# ESP32.net
KiCad netlist of a schematic drawn in Altium Designer
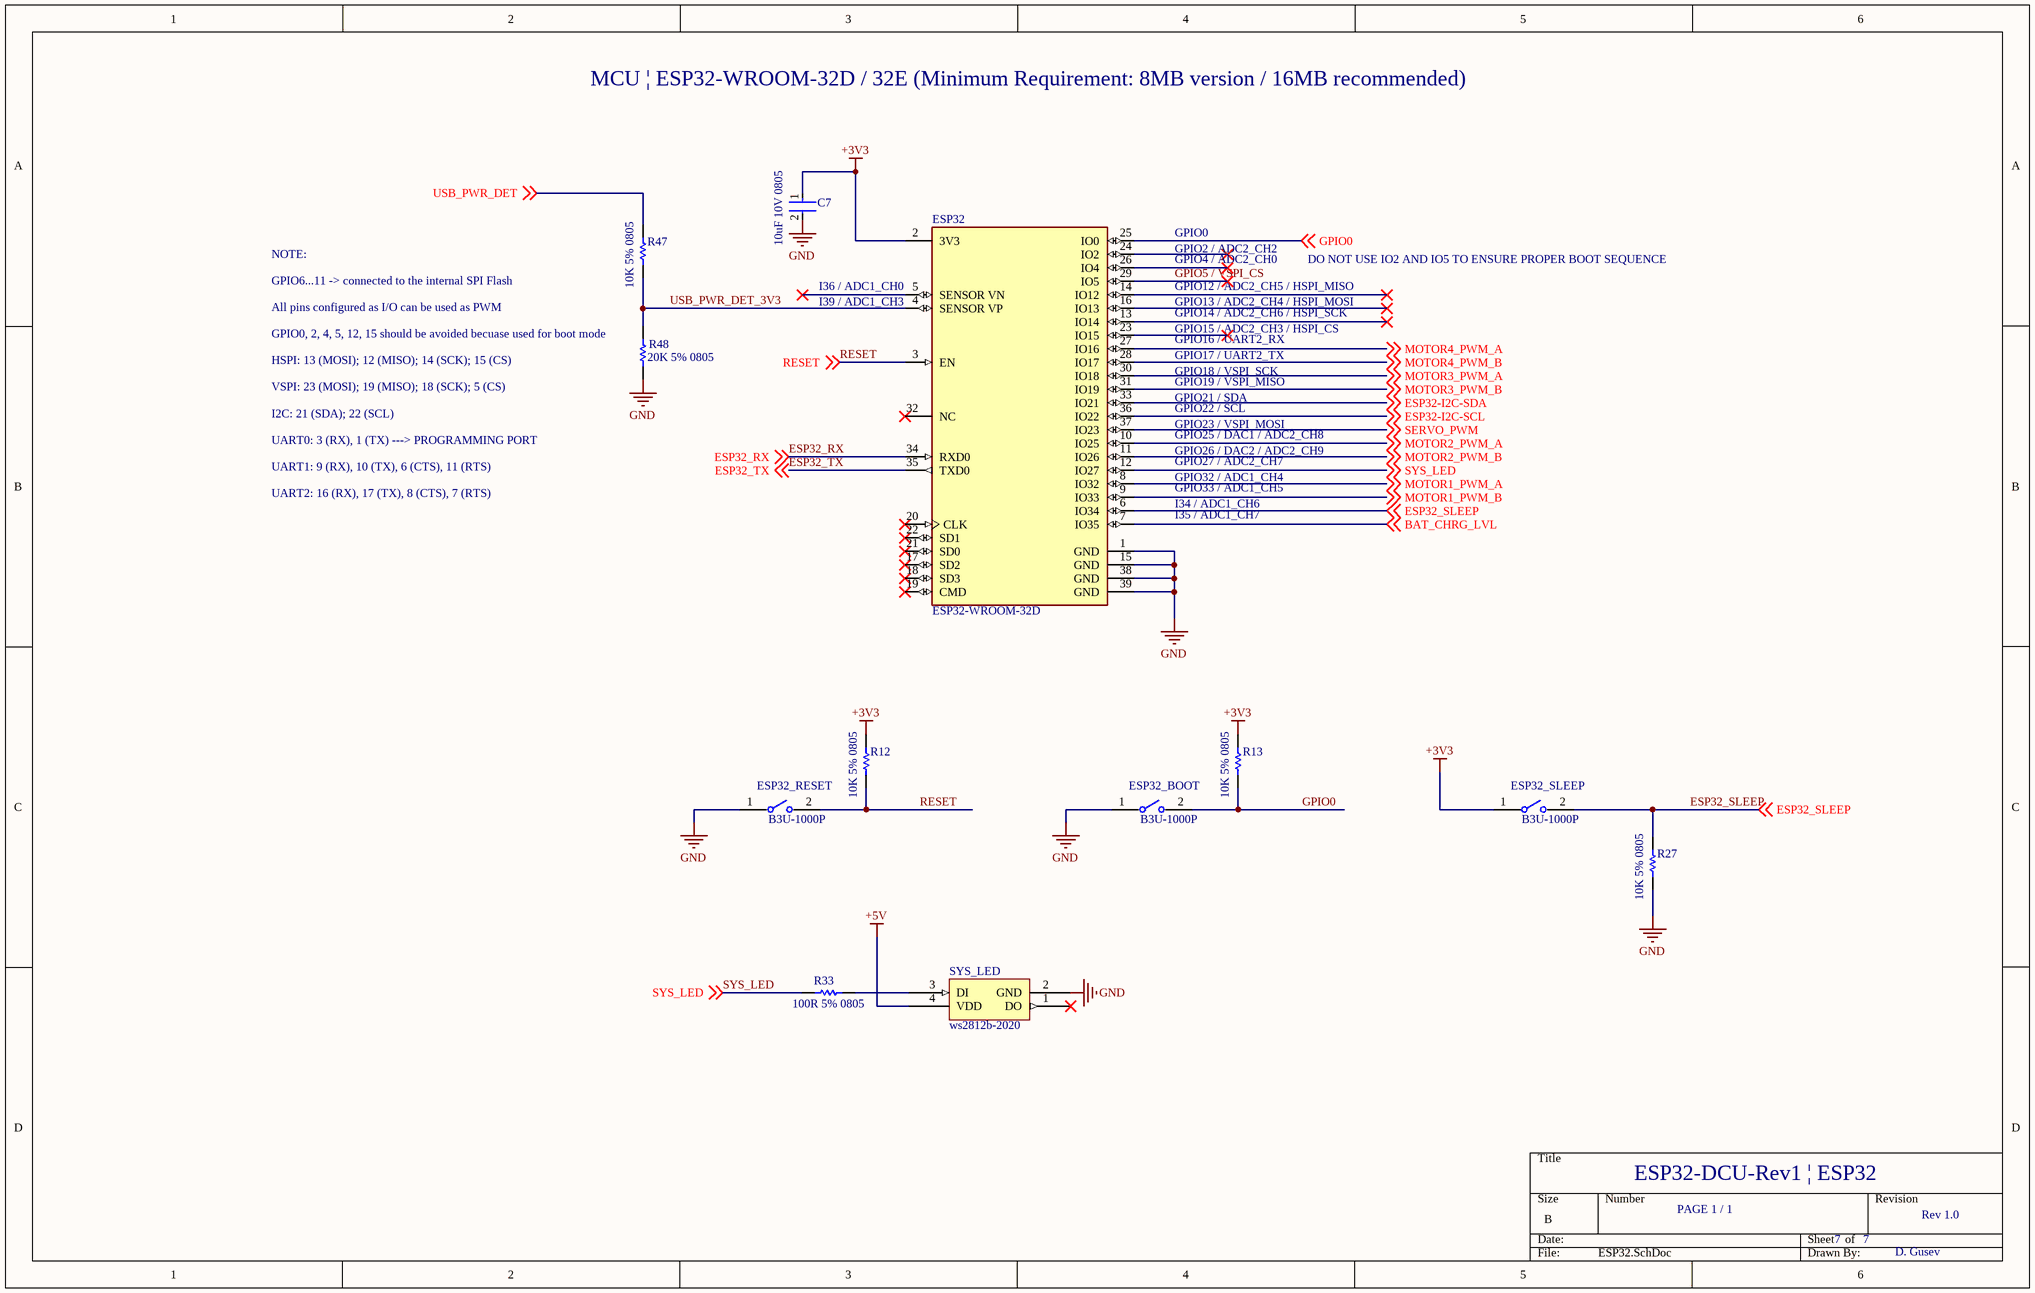
[diagram p0: ESP32.SchDoc]

(export (version "E")
  (design (tool "Eeschema 10.0.6"))
  (components
    (comp (ref "C7")
      (value "10uF 10V 0805")
      (footprint "FP-C0805C-DG-MFG")
      (description "CAP CER 10UF 10V X5R 0805")
      (fields (field (name "TOLERANCE") "10%") (field (name "MANUFACTURER PART NUMBER") "C0805C106K8PACTU"))
      (libsource (lib "Altium Content Vault") (part "11868f565c42a9108669ba33697ecf6"))
    )
    (comp (ref "ESP32")
      (value "ESP32-WROOM-32D")
      (footprint "ESP32-WROOM-U")
      (description "WIFI MODULE 32MBITS SPI FLASH")
      (fields
        (field (name "OCTOPART") "https://octopart.com/esp32-wroom-32d-espressif+systems-91040050")
        (field (name "MANUFACTURER") "Espressif Systems")
      )
      (libsource (lib "ddrlegobrick") (part "ESP32-WROOM-U"))
    )
    (comp (ref "ESP32_BOOT")
      (value "B3U-1000P")
      (footprint "FP-B3U-1000P-MFG")
      (description "SWITCH TACTILE SPST-NO 0.05A 12V")
      (libsource (lib "Altium Content Vault") (part "ae622034201233ca1abcedc05908f33"))
    )
    (comp (ref "ESP32_RESET")
      (value "B3U-1000P")
      (footprint "FP-B3U-1000P-MFG")
      (description "SWITCH TACTILE SPST-NO 0.05A 12V")
      (libsource (lib "Altium Content Vault") (part "ae622034201233ca1abcedc05908f33"))
    )
    (comp (ref "ESP32_SLEEP")
      (value "B3U-1000P")
      (footprint "FP-B3U-1000P-MFG")
      (description "SWITCH TACTILE SPST-NO 0.05A 12V")
      (libsource (lib "Altium Content Vault") (part "ae622034201233ca1abcedc05908f33"))
    )
    (comp (ref "R12")
      (value "10K 5% 0805")
      (footprint "RESC2013X60X40ML20T25")
      (fields (field (name "PART NUMBER") "ERA6AEB123V") (field (name "MANUFACTURER") "Panasonic"))
      (libsource (lib "Altium Content Vault") (part "RES"))
    )
    (comp (ref "R13")
      (value "10K 5% 0805")
      (footprint "RESC2013X60X40ML20T25")
      (fields (field (name "PART NUMBER") "ERA6AEB123V") (field (name "MANUFACTURER") "Panasonic"))
      (libsource (lib "Altium Content Vault") (part "RES"))
    )
    (comp (ref "R27")
      (value "10K 5% 0805")
      (footprint "RESC2013X60X40ML20T25")
      (fields (field (name "PART NUMBER") "ERA6AEB123V") (field (name "MANUFACTURER") "Panasonic"))
      (libsource (lib "Altium Content Vault") (part "RES"))
    )
    (comp (ref "R33")
      (value "100R 5% 0805")
      (footprint "RESC2013X60X35ML10T20")
      (description "Chip Resistor, 100 Ohm, +/-1%, 0.125 W, -55 to 155 degC, 0805 (2012 Metric), RoHS, Tape and Reel")
      (fields (field (name "TOLERANCE") "1%") (field (name "MANUFACTURER") "Yageo"))
      (libsource (lib "Altium Content Vault") (part "RES-2"))
    )
    (comp (ref "R47")
      (value "10K 5% 0805")
      (footprint "RESC2013X60X40ML20T25")
      (fields (field (name "PART NUMBER") "ERA6AEB123V") (field (name "MANUFACTURER") "Panasonic"))
      (libsource (lib "Altium Content Vault") (part "RES"))
    )
    (comp (ref "R48")
      (value "20K 5% 0805")
      (footprint "RESC0805(2012)_N")
      (description "20K 0.125W 1% 0805 (2012 Metric)  SMD")
      (fields (field (name "POWER") "0.125 W") (field (name "TOLERANCE") "1 %"))
      (libsource (lib "Altium Content Vault") (part "RES"))
    )
    (comp (ref "SYS_LED")
      (value "ws2812b-2020")
      (footprint "ws2812b")
      (libsource (lib "ddrlegobrick") (part "ws2812b-2020"))
    )
  )
  (nets
    (net (code "1") (name "+3V3") (class "Default")
      (node (ref "C7") (pin "1") (pinfunction "1_1") (pintype "passive"))
      (node (ref "ESP32") (pin "2") (pinfunction "3V3_2") (pintype "power_in"))
      (node (ref "ESP32_SLEEP") (pin "1") (pinfunction "1_1") (pintype "passive"))
      (node (ref "R12") (pin "2") (pinfunction "2_2") (pintype "passive"))
      (node (ref "R13") (pin "2") (pinfunction "2_2") (pintype "passive"))
    )
    (net (code "2") (name "+5V") (class "Default")
      (node (ref "SYS_LED") (pin "4") (pinfunction "VDD_4") (pintype "power_in"))
    )
    (net (code "3") (name "/GPIO5 {slash} VSPI_CS") (class "Default")
      (node (ref "ESP32") (pin "29") (pinfunction "IO5_29") (pintype "bidirectional+no_connect"))
    )
    (net (code "4") (name "/USB_PWR_DET_3V3") (class "Default")
      (node (ref "ESP32") (pin "4") (pinfunction "SENSOR_VP_4") (pintype "bidirectional"))
      (node (ref "R47") (pin "1") (pinfunction "1_1") (pintype "passive"))
      (node (ref "R48") (pin "2") (pinfunction "2_2") (pintype "passive"))
    )
    (net (code "5") (name "BAT_CHRG_LVL") (class "Default")
      (node (ref "ESP32") (pin "7") (pinfunction "IO35_7") (pintype "bidirectional"))
    )
    (net (code "6") (name "ESP32-I2C-SCL") (class "Default")
      (node (ref "ESP32") (pin "36") (pinfunction "IO22_36") (pintype "bidirectional"))
    )
    (net (code "7") (name "ESP32-I2C-SDA") (class "Default")
      (node (ref "ESP32") (pin "33") (pinfunction "IO21_33") (pintype "bidirectional"))
    )
    (net (code "8") (name "ESP32_RX") (class "Default")
      (node (ref "ESP32") (pin "34") (pinfunction "RXD0_34") (pintype "input"))
    )
    (net (code "9") (name "ESP32_SLEEP") (class "Default")
      (node (ref "ESP32") (pin "6") (pinfunction "IO34_6") (pintype "bidirectional"))
      (node (ref "ESP32_SLEEP") (pin "2") (pinfunction "2_2") (pintype "passive"))
      (node (ref "R27") (pin "2") (pinfunction "2_2") (pintype "passive"))
    )
    (net (code "10") (name "ESP32_TX") (class "Default")
      (node (ref "ESP32") (pin "35") (pinfunction "TXD0_35") (pintype "output"))
    )
    (net (code "11") (name "GND") (class "Default")
      (node (ref "C7") (pin "2") (pinfunction "2_2") (pintype "passive"))
      (node (ref "ESP32") (pin "1") (pinfunction "GND_1") (pintype "power_in"))
      (node (ref "ESP32") (pin "15") (pinfunction "GND_15") (pintype "power_in"))
      (node (ref "ESP32") (pin "38") (pinfunction "GND_38") (pintype "power_in"))
      (node (ref "ESP32") (pin "39") (pinfunction "GND_39") (pintype "power_in"))
      (node (ref "ESP32_BOOT") (pin "1") (pinfunction "1_1") (pintype "passive"))
      (node (ref "ESP32_RESET") (pin "1") (pinfunction "1_1") (pintype "passive"))
      (node (ref "R27") (pin "1") (pinfunction "1_1") (pintype "passive"))
      (node (ref "R48") (pin "1") (pinfunction "1_1") (pintype "passive"))
      (node (ref "SYS_LED") (pin "2") (pinfunction "GND_2") (pintype "passive"))
    )
    (net (code "12") (name "GPIO0") (class "Default")
      (node (ref "ESP32") (pin "25") (pinfunction "IO0_25") (pintype "bidirectional"))
      (node (ref "ESP32_BOOT") (pin "2") (pinfunction "2_2") (pintype "passive"))
      (node (ref "R13") (pin "1") (pinfunction "1_1") (pintype "passive"))
    )
    (net (code "13") (name "MOTOR1_PWM_A") (class "Default")
      (node (ref "ESP32") (pin "8") (pinfunction "IO32_8") (pintype "bidirectional"))
    )
    (net (code "14") (name "MOTOR1_PWM_B") (class "Default")
      (node (ref "ESP32") (pin "9") (pinfunction "IO33_9") (pintype "bidirectional"))
    )
    (net (code "15") (name "MOTOR2_PWM_A") (class "Default")
      (node (ref "ESP32") (pin "10") (pinfunction "IO25_10") (pintype "bidirectional"))
    )
    (net (code "16") (name "MOTOR2_PWM_B") (class "Default")
      (node (ref "ESP32") (pin "11") (pinfunction "IO26_11") (pintype "bidirectional"))
    )
    (net (code "17") (name "MOTOR3_PWM_A") (class "Default")
      (node (ref "ESP32") (pin "30") (pinfunction "IO18_30") (pintype "bidirectional"))
    )
    (net (code "18") (name "MOTOR3_PWM_B") (class "Default")
      (node (ref "ESP32") (pin "31") (pinfunction "IO19_31") (pintype "bidirectional"))
    )
    (net (code "19") (name "MOTOR4_PWM_A") (class "Default")
      (node (ref "ESP32") (pin "27") (pinfunction "IO16_27") (pintype "bidirectional"))
    )
    (net (code "20") (name "MOTOR4_PWM_B") (class "Default")
      (node (ref "ESP32") (pin "28") (pinfunction "IO17_28") (pintype "bidirectional"))
    )
    (net (code "21") (name "Net-(SYS_LED-DI)") (class "Default")
      (node (ref "R33") (pin "2") (pinfunction "2_2") (pintype "passive"))
      (node (ref "SYS_LED") (pin "3") (pinfunction "DI_3") (pintype "input"))
    )
    (net (code "22") (name "RESET") (class "Default")
      (node (ref "ESP32") (pin "3") (pinfunction "EN_3") (pintype "input"))
      (node (ref "ESP32_RESET") (pin "2") (pinfunction "2_2") (pintype "passive"))
      (node (ref "R12") (pin "1") (pinfunction "1_1") (pintype "passive"))
    )
    (net (code "23") (name "SERVO_PWM") (class "Default")
      (node (ref "ESP32") (pin "37") (pinfunction "IO23_37") (pintype "bidirectional"))
    )
    (net (code "24") (name "SYS_LED") (class "Default")
      (node (ref "ESP32") (pin "12") (pinfunction "IO27_12") (pintype "bidirectional"))
      (node (ref "R33") (pin "1") (pinfunction "1_1") (pintype "passive"))
    )
    (net (code "25") (name "USB_PWR_DET") (class "Default")
      (node (ref "R47") (pin "2") (pinfunction "2_2") (pintype "passive"))
    )
    (net (code "26") (name "unconnected-(ESP32-CLK-Pad20)") (class "Default")
      (node (ref "ESP32") (pin "20") (pinfunction "CLK_20") (pintype "input+no_connect"))
    )
    (net (code "27") (name "unconnected-(ESP32-CMD-Pad19)") (class "Default")
      (node (ref "ESP32") (pin "19") (pinfunction "CMD_19") (pintype "bidirectional+no_connect"))
    )
    (net (code "28") (name "unconnected-(ESP32-IO2-Pad24)") (class "Default")
      (node (ref "ESP32") (pin "24") (pinfunction "IO2_24") (pintype "bidirectional+no_connect"))
    )
    (net (code "29") (name "unconnected-(ESP32-IO4-Pad26)") (class "Default")
      (node (ref "ESP32") (pin "26") (pinfunction "IO4_26") (pintype "bidirectional+no_connect"))
    )
    (net (code "30") (name "unconnected-(ESP32-IO12-Pad14)") (class "Default")
      (node (ref "ESP32") (pin "14") (pinfunction "IO12_14") (pintype "bidirectional+no_connect"))
    )
    (net (code "31") (name "unconnected-(ESP32-IO13-Pad16)") (class "Default")
      (node (ref "ESP32") (pin "16") (pinfunction "IO13_16") (pintype "bidirectional+no_connect"))
    )
    (net (code "32") (name "unconnected-(ESP32-IO14-Pad13)") (class "Default")
      (node (ref "ESP32") (pin "13") (pinfunction "IO14_13") (pintype "bidirectional+no_connect"))
    )
    (net (code "33") (name "unconnected-(ESP32-IO15-Pad23)") (class "Default")
      (node (ref "ESP32") (pin "23") (pinfunction "IO15_23") (pintype "bidirectional+no_connect"))
    )
    (net (code "34") (name "unconnected-(ESP32-NC-Pad32)") (class "Default")
      (node (ref "ESP32") (pin "32") (pinfunction "NC_32") (pintype "passive+no_connect"))
    )
    (net (code "35") (name "unconnected-(ESP32-SD0-Pad21)") (class "Default")
      (node (ref "ESP32") (pin "21") (pinfunction "SD0_21") (pintype "bidirectional+no_connect"))
    )
    (net (code "36") (name "unconnected-(ESP32-SD1-Pad22)") (class "Default")
      (node (ref "ESP32") (pin "22") (pinfunction "SD1_22") (pintype "bidirectional+no_connect"))
    )
    (net (code "37") (name "unconnected-(ESP32-SD2-Pad17)") (class "Default")
      (node (ref "ESP32") (pin "17") (pinfunction "SD2_17") (pintype "bidirectional+no_connect"))
    )
    (net (code "38") (name "unconnected-(ESP32-SD3-Pad18)") (class "Default")
      (node (ref "ESP32") (pin "18") (pinfunction "SD3_18") (pintype "bidirectional+no_connect"))
    )
    (net (code "39") (name "unconnected-(ESP32-SENSOR_VN-Pad5)") (class "Default")
      (node (ref "ESP32") (pin "5") (pinfunction "SENSOR_VN_5") (pintype "bidirectional+no_connect"))
    )
    (net (code "40") (name "unconnected-(SYS_LED-DO-Pad1)") (class "Default")
      (node (ref "SYS_LED") (pin "1") (pinfunction "DO_1") (pintype "output+no_connect"))
    )
  )
)
